# v002.net
KiCad netlist of a schematic drawn in EAGLE
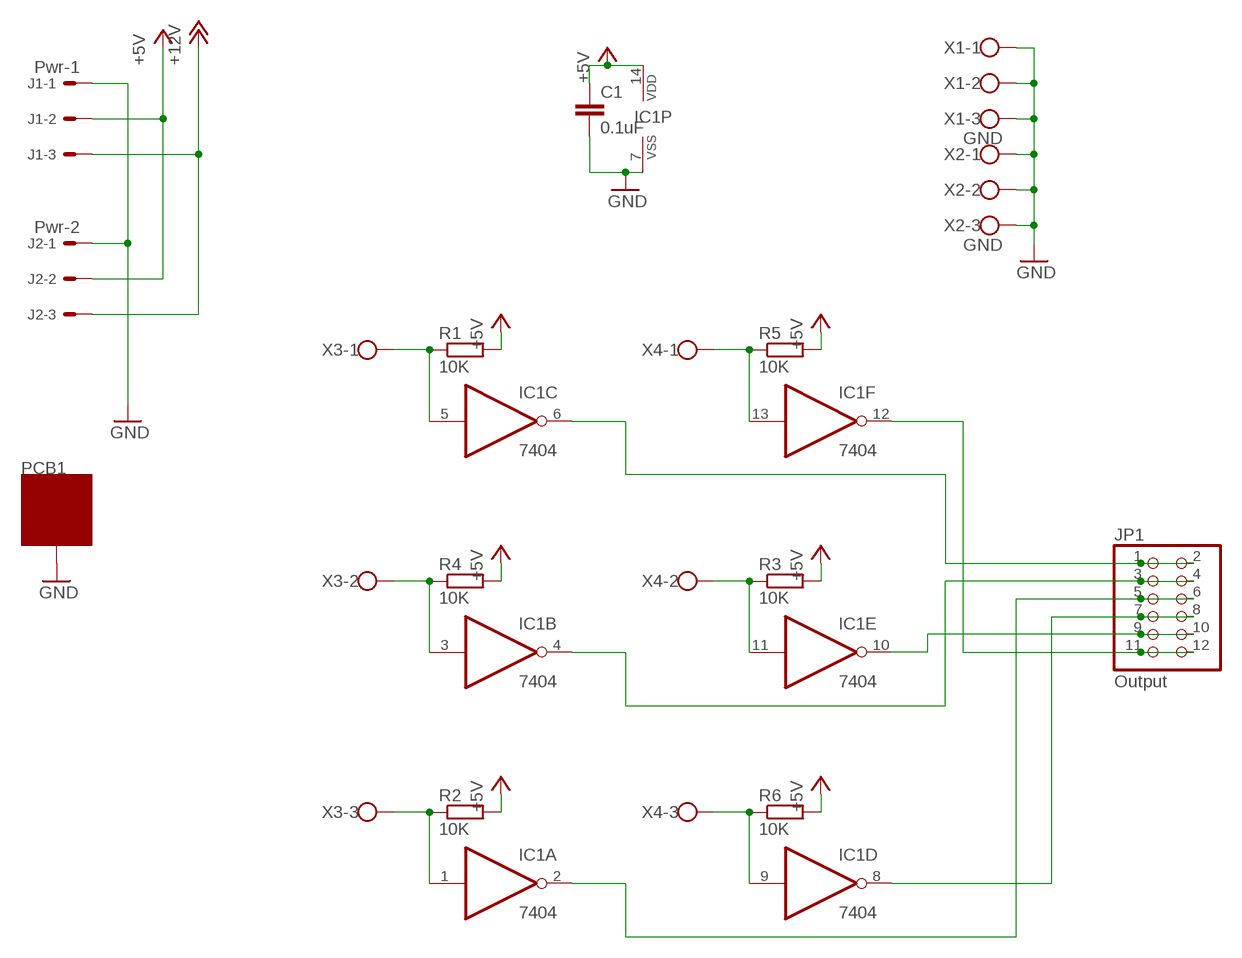
[diagram p0: schematic, sheet 1]

(export (version "E")
  (design (tool "Eeschema 10.0.6"))
  (components
    (comp (ref "C1")
      (value "0.1uF")
      (footprint "eagle-import:C050-024X044")
      (libsource (lib "eagle-import") (part "C-EU050-024X044"))
    )
    (comp (ref "IC1")
      (value "7404")
      (footprint "eagle-import:DIL14")
      (libsource (lib "eagle-import") (part "4584N"))
    )
    (comp (ref "J1")
      (value "Pwr-1")
      (footprint "eagle-import:6410-03")
      (libsource (lib "eagle-import") (part "22-?-0327-2031"))
    )
    (comp (ref "J2")
      (value "Pwr-2")
      (footprint "eagle-import:6410-03")
      (libsource (lib "eagle-import") (part "22-?-0327-2031"))
    )
    (comp (ref "JP1")
      (value "Output")
      (footprint "eagle-import:2X06")
      (libsource (lib "eagle-import") (part "PINHD-2X6"))
    )
    (comp (ref "PCB1")
      (value "ZZZ_MODULE05X05")
      (footprint "eagle-import:ZZZ_MODULE_05X05")
      (libsource (lib "eagle-import") (part "ZZZ_MODULE05X05"))
    )
    (comp (ref "R1")
      (value "10K")
      (footprint "eagle-import:0207_2V")
      (libsource (lib "eagle-import") (part "R-EU_0207/2V"))
    )
    (comp (ref "R2")
      (value "10K")
      (footprint "eagle-import:0207_2V")
      (libsource (lib "eagle-import") (part "R-EU_0207/2V"))
    )
    (comp (ref "R3")
      (value "10K")
      (footprint "eagle-import:0207_2V")
      (libsource (lib "eagle-import") (part "R-EU_0207/2V"))
    )
    (comp (ref "R4")
      (value "10K")
      (footprint "eagle-import:0207_2V")
      (libsource (lib "eagle-import") (part "R-EU_0207/2V"))
    )
    (comp (ref "R5")
      (value "10K")
      (footprint "eagle-import:0207_2V")
      (libsource (lib "eagle-import") (part "R-EU_0207/2V"))
    )
    (comp (ref "R6")
      (value "10K")
      (footprint "eagle-import:0207_2V")
      (libsource (lib "eagle-import") (part "R-EU_0207/2V"))
    )
    (comp (ref "X1")
      (value "GND")
      (footprint "eagle-import:W237-103")
      (fields (field (name "MPN") "237-103"))
      (libsource (lib "eagle-import") (part "W237-103"))
    )
    (comp (ref "X2")
      (value "GND")
      (footprint "eagle-import:W237-103")
      (fields (field (name "MPN") "237-103"))
      (libsource (lib "eagle-import") (part "W237-103"))
    )
    (comp (ref "X3")
      (value "W237-103")
      (footprint "eagle-import:W237-103")
      (fields (field (name "MPN") "237-103"))
      (libsource (lib "eagle-import") (part "W237-103"))
    )
    (comp (ref "X4")
      (value "W237-103")
      (footprint "eagle-import:W237-103")
      (fields (field (name "MPN") "237-103"))
      (libsource (lib "eagle-import") (part "W237-103"))
    )
  )
  (nets
    (net (code "1") (name "+5V") (class "Default")
      (node (ref "C1") (pin "1") (pinfunction "1_1") (pintype "passive"))
      (node (ref "IC1") (pin "14") (pinfunction "VDD_14") (pintype "power_in"))
      (node (ref "J1") (pin "2") (pinfunction "S_2") (pintype "passive"))
      (node (ref "J2") (pin "2") (pinfunction "S_2") (pintype "passive"))
      (node (ref "R1") (pin "2") (pinfunction "2_2") (pintype "passive"))
      (node (ref "R2") (pin "2") (pinfunction "2_2") (pintype "passive"))
      (node (ref "R3") (pin "2") (pinfunction "2_2") (pintype "passive"))
      (node (ref "R4") (pin "2") (pinfunction "2_2") (pintype "passive"))
      (node (ref "R5") (pin "2") (pinfunction "2_2") (pintype "passive"))
      (node (ref "R6") (pin "2") (pinfunction "2_2") (pintype "passive"))
    )
    (net (code "2") (name "+12V") (class "Default")
      (node (ref "J1") (pin "3") (pinfunction "S_3") (pintype "passive"))
      (node (ref "J2") (pin "3") (pinfunction "S_3") (pintype "passive"))
    )
    (net (code "3") (name "GND") (class "Default")
      (node (ref "C1") (pin "2") (pinfunction "2_2") (pintype "passive"))
      (node (ref "IC1") (pin "7") (pinfunction "VSS_7") (pintype "power_in"))
      (node (ref "J1") (pin "1") (pinfunction "S_1") (pintype "passive"))
      (node (ref "J2") (pin "1") (pinfunction "S_1") (pintype "passive"))
      (node (ref "PCB1") (pin "GND@1") (pinfunction "GND_GND@1") (pintype "power_in"))
      (node (ref "PCB1") (pin "GND@2") (pinfunction "GND_GND@2") (pintype "power_in"))
      (node (ref "PCB1") (pin "GND@3") (pinfunction "GND_GND@3") (pintype "power_in"))
      (node (ref "PCB1") (pin "GND@4") (pinfunction "GND_GND@4") (pintype "power_in"))
      (node (ref "PCB1") (pin "GND@5") (pinfunction "GND_GND@5") (pintype "power_in"))
      (node (ref "PCB1") (pin "GND@6") (pinfunction "GND_GND@6") (pintype "power_in"))
      (node (ref "PCB1") (pin "GND@7") (pinfunction "GND_GND@7") (pintype "power_in"))
      (node (ref "PCB1") (pin "GND@8") (pinfunction "GND_GND@8") (pintype "power_in"))
      (node (ref "X1") (pin "1") (pinfunction "KL_1") (pintype "passive"))
      (node (ref "X1") (pin "2") (pinfunction "KL_2") (pintype "passive"))
      (node (ref "X1") (pin "3") (pinfunction "KL_3") (pintype "passive"))
      (node (ref "X2") (pin "1") (pinfunction "KL_1") (pintype "passive"))
      (node (ref "X2") (pin "2") (pinfunction "KL_2") (pintype "passive"))
      (node (ref "X2") (pin "3") (pinfunction "KL_3") (pintype "passive"))
    )
    (net (code "4") (name "Net-(IC1A-I)") (class "Default")
      (node (ref "IC1") (pin "1") (pinfunction "I_1") (pintype "input"))
      (node (ref "R2") (pin "1") (pinfunction "1_1") (pintype "passive"))
      (node (ref "X3") (pin "3") (pinfunction "KL_3") (pintype "passive"))
    )
    (net (code "5") (name "Net-(IC1A-O)") (class "Default")
      (node (ref "IC1") (pin "2") (pinfunction "O_2") (pintype "output"))
      (node (ref "JP1") (pin "5") (pinfunction "5_5") (pintype "passive"))
      (node (ref "JP1") (pin "6") (pinfunction "6_6") (pintype "passive"))
    )
    (net (code "6") (name "Net-(IC1B-I)") (class "Default")
      (node (ref "IC1") (pin "3") (pinfunction "I_3") (pintype "input"))
      (node (ref "R4") (pin "1") (pinfunction "1_1") (pintype "passive"))
      (node (ref "X3") (pin "2") (pinfunction "KL_2") (pintype "passive"))
    )
    (net (code "7") (name "Net-(IC1B-O)") (class "Default")
      (node (ref "IC1") (pin "4") (pinfunction "O_4") (pintype "output"))
      (node (ref "JP1") (pin "3") (pinfunction "3_3") (pintype "passive"))
      (node (ref "JP1") (pin "4") (pinfunction "4_4") (pintype "passive"))
    )
    (net (code "8") (name "Net-(IC1C-I)") (class "Default")
      (node (ref "IC1") (pin "5") (pinfunction "I_5") (pintype "input"))
      (node (ref "R1") (pin "1") (pinfunction "1_1") (pintype "passive"))
      (node (ref "X3") (pin "1") (pinfunction "KL_1") (pintype "passive"))
    )
    (net (code "9") (name "Net-(IC1C-O)") (class "Default")
      (node (ref "IC1") (pin "6") (pinfunction "O_6") (pintype "output"))
      (node (ref "JP1") (pin "1") (pinfunction "1_1") (pintype "passive"))
      (node (ref "JP1") (pin "2") (pinfunction "2_2") (pintype "passive"))
    )
    (net (code "10") (name "Net-(IC1D-I)") (class "Default")
      (node (ref "IC1") (pin "9") (pinfunction "I_9") (pintype "input"))
      (node (ref "R6") (pin "1") (pinfunction "1_1") (pintype "passive"))
      (node (ref "X4") (pin "3") (pinfunction "KL_3") (pintype "passive"))
    )
    (net (code "11") (name "Net-(IC1D-O)") (class "Default")
      (node (ref "IC1") (pin "8") (pinfunction "O_8") (pintype "output"))
      (node (ref "JP1") (pin "7") (pinfunction "7_7") (pintype "passive"))
      (node (ref "JP1") (pin "8") (pinfunction "8_8") (pintype "passive"))
    )
    (net (code "12") (name "Net-(IC1E-I)") (class "Default")
      (node (ref "IC1") (pin "11") (pinfunction "I_11") (pintype "input"))
      (node (ref "R3") (pin "1") (pinfunction "1_1") (pintype "passive"))
      (node (ref "X4") (pin "2") (pinfunction "KL_2") (pintype "passive"))
    )
    (net (code "13") (name "Net-(IC1E-O)") (class "Default")
      (node (ref "IC1") (pin "10") (pinfunction "O_10") (pintype "output"))
      (node (ref "JP1") (pin "10") (pinfunction "10_10") (pintype "passive"))
      (node (ref "JP1") (pin "9") (pinfunction "9_9") (pintype "passive"))
    )
    (net (code "14") (name "Net-(IC1F-I)") (class "Default")
      (node (ref "IC1") (pin "13") (pinfunction "I_13") (pintype "input"))
      (node (ref "R5") (pin "1") (pinfunction "1_1") (pintype "passive"))
      (node (ref "X4") (pin "1") (pinfunction "KL_1") (pintype "passive"))
    )
    (net (code "15") (name "Net-(IC1F-O)") (class "Default")
      (node (ref "IC1") (pin "12") (pinfunction "O_12") (pintype "output"))
      (node (ref "JP1") (pin "11") (pinfunction "11_11") (pintype "passive"))
      (node (ref "JP1") (pin "12") (pinfunction "12_12") (pintype "passive"))
    )
  )
)
